# H22R2x_Frontend_2.net
KiCad netlist of a schematic drawn in Altium Designer
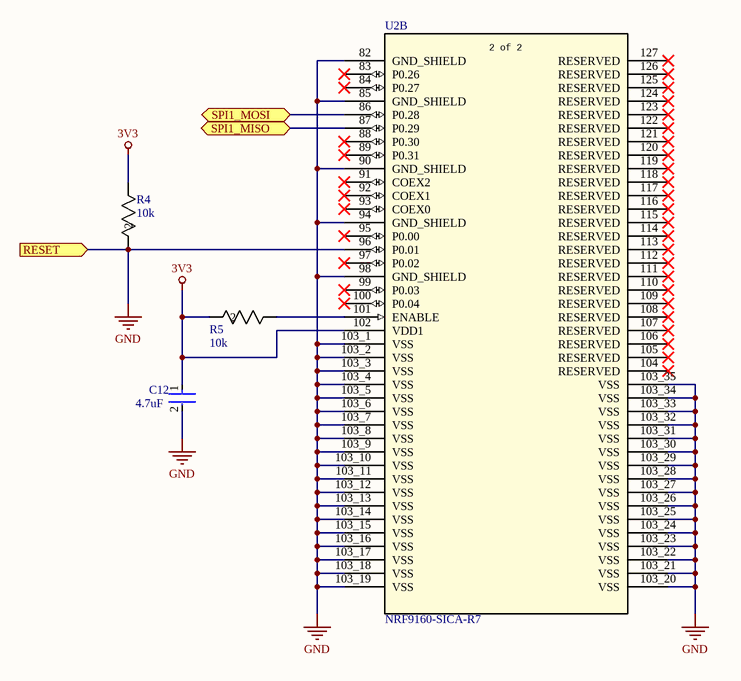
[diagram p0: H22R2x_Frontend 2.SchDoc]

(export (version "E")
  (design (tool "Eeschema 10.0.6"))
  (components
    (comp (ref "C12")
      (value "4.7uF")
      (footprint "FP-0603-L_1_6_0_15-W_0_8-MFG")
      (description "Ceramic Capacitor General Use 4.7uF ±10% 10V X6S 0603")
      (fields (field (name "TOLERANCE") "10%"))
      (libsource (lib "Altium Content Vault") (part "11868f565c42a9108669ba33697ecf6"))
    )
    (comp (ref "R4")
      (value "10k")
      (footprint "RC0201N_VIS")
      (description "CRCW0201 200 10K 1% ET7 e3")
      (fields
        (field (name "MANUFACTURER_PART_NUMBER") "CRCW020110K0FNED")
        (field (name "COPYRIGHT") "Copyright (C) 2025 Ultra Librarian. All rights reserved.")
      )
      (libsource (lib "Tyme Hopkins") (part "CRCW020110K0FNED"))
    )
    (comp (ref "R5")
      (value "10k")
      (footprint "RC0201N_VIS")
      (description "CRCW0201 200 10K 1% ET7 e3")
      (fields
        (field (name "MANUFACTURER_PART_NUMBER") "CRCW020110K0FNED")
        (field (name "COPYRIGHT") "Copyright (C) 2025 Ultra Librarian. All rights reserved.")
      )
      (libsource (lib "Tyme Hopkins") (part "CRCW020110K0FNED"))
    )
    (comp (ref "U2")
      (value "NRF9160-SICA-R7")
      (footprint "LGA127_16p00X10p50_nRF9160_NOR")
      (description "Description")
      (fields (field (name "COPYRIGHT") "Copyright (C) 2025 Ultra Librarian. All rights reserved."))
      (libsource (lib "Tyme Hopkins") (part "NRF9160-SICA-R7"))
    )
  )
  (nets
    (net (code "1") (name "/SPI1_MISO") (class "Default")
      (node (ref "U2") (pin "87") (pinfunction "P0.29_87") (pintype "bidirectional"))
    )
    (net (code "2") (name "/SPI1_MOSI") (class "Default")
      (node (ref "U2") (pin "86") (pinfunction "P0.28_86") (pintype "bidirectional"))
    )
    (net (code "3") (name "3V3") (class "Default")
      (node (ref "C12") (pin "1") (pinfunction "1_1") (pintype "passive"))
      (node (ref "R4") (pin "1") (pinfunction "1_1") (pintype "passive"))
      (node (ref "R5") (pin "2") (pinfunction "2_2") (pintype "passive"))
      (node (ref "U2") (pin "102") (pinfunction "VDD1_102") (pintype "power_in"))
    )
    (net (code "4") (name "GND") (class "Default")
      (node (ref "C12") (pin "2") (pinfunction "2_2") (pintype "passive"))
      (node (ref "R4") (pin "2") (pinfunction "2_2") (pintype "passive"))
      (node (ref "U2") (pin "103_1") (pinfunction "VSS_103_1") (pintype "power_in"))
      (node (ref "U2") (pin "103_10") (pinfunction "VSS_103_10") (pintype "power_in"))
      (node (ref "U2") (pin "103_11") (pinfunction "VSS_103_11") (pintype "power_in"))
      (node (ref "U2") (pin "103_12") (pinfunction "VSS_103_12") (pintype "power_in"))
      (node (ref "U2") (pin "103_13") (pinfunction "VSS_103_13") (pintype "power_in"))
      (node (ref "U2") (pin "103_14") (pinfunction "VSS_103_14") (pintype "power_in"))
      (node (ref "U2") (pin "103_15") (pinfunction "VSS_103_15") (pintype "power_in"))
      (node (ref "U2") (pin "103_16") (pinfunction "VSS_103_16") (pintype "power_in"))
      (node (ref "U2") (pin "103_17") (pinfunction "VSS_103_17") (pintype "power_in"))
      (node (ref "U2") (pin "103_18") (pinfunction "VSS_103_18") (pintype "power_in"))
      (node (ref "U2") (pin "103_19") (pinfunction "VSS_103_19") (pintype "power_in"))
      (node (ref "U2") (pin "103_2") (pinfunction "VSS_103_2") (pintype "power_in"))
      (node (ref "U2") (pin "103_20") (pinfunction "VSS_103_20") (pintype "power_in"))
      (node (ref "U2") (pin "103_21") (pinfunction "VSS_103_21") (pintype "power_in"))
      (node (ref "U2") (pin "103_22") (pinfunction "VSS_103_22") (pintype "power_in"))
      (node (ref "U2") (pin "103_23") (pinfunction "VSS_103_23") (pintype "power_in"))
      (node (ref "U2") (pin "103_24") (pinfunction "VSS_103_24") (pintype "power_in"))
      (node (ref "U2") (pin "103_25") (pinfunction "VSS_103_25") (pintype "power_in"))
      (node (ref "U2") (pin "103_26") (pinfunction "VSS_103_26") (pintype "power_in"))
      (node (ref "U2") (pin "103_27") (pinfunction "VSS_103_27") (pintype "power_in"))
      (node (ref "U2") (pin "103_28") (pinfunction "VSS_103_28") (pintype "power_in"))
      (node (ref "U2") (pin "103_29") (pinfunction "VSS_103_29") (pintype "power_in"))
      (node (ref "U2") (pin "103_3") (pinfunction "VSS_103_3") (pintype "power_in"))
      (node (ref "U2") (pin "103_30") (pinfunction "VSS_103_30") (pintype "power_in"))
      (node (ref "U2") (pin "103_31") (pinfunction "VSS_103_31") (pintype "power_in"))
      (node (ref "U2") (pin "103_32") (pinfunction "VSS_103_32") (pintype "power_in"))
      (node (ref "U2") (pin "103_33") (pinfunction "VSS_103_33") (pintype "power_in"))
      (node (ref "U2") (pin "103_34") (pinfunction "VSS_103_34") (pintype "power_in"))
      (node (ref "U2") (pin "103_35") (pinfunction "VSS_103_35") (pintype "power_in"))
      (node (ref "U2") (pin "103_4") (pinfunction "VSS_103_4") (pintype "power_in"))
      (node (ref "U2") (pin "103_5") (pinfunction "VSS_103_5") (pintype "power_in"))
      (node (ref "U2") (pin "103_6") (pinfunction "VSS_103_6") (pintype "power_in"))
      (node (ref "U2") (pin "103_7") (pinfunction "VSS_103_7") (pintype "power_in"))
      (node (ref "U2") (pin "103_8") (pinfunction "VSS_103_8") (pintype "power_in"))
      (node (ref "U2") (pin "103_9") (pinfunction "VSS_103_9") (pintype "power_in"))
      (node (ref "U2") (pin "82") (pinfunction "GND_SHIELD_82") (pintype "power_in"))
      (node (ref "U2") (pin "85") (pinfunction "GND_SHIELD_85") (pintype "power_in"))
      (node (ref "U2") (pin "90") (pinfunction "GND_SHIELD_90") (pintype "power_in"))
      (node (ref "U2") (pin "94") (pinfunction "GND_SHIELD_94") (pintype "power_in"))
      (node (ref "U2") (pin "96") (pinfunction "P0.01_96") (pintype "bidirectional"))
      (node (ref "U2") (pin "98") (pinfunction "GND_SHIELD_98") (pintype "power_in"))
    )
    (net (code "5") (name "Net-(U2B-ENABLE)") (class "Default")
      (node (ref "R5") (pin "1") (pinfunction "1_1") (pintype "passive"))
      (node (ref "U2") (pin "101") (pinfunction "ENABLE_101") (pintype "input"))
    )
    (net (code "6") (name "unconnected-(U2B-COEX0-Pad93)") (class "Default")
      (node (ref "U2") (pin "93") (pinfunction "COEX0_93") (pintype "bidirectional+no_connect"))
    )
    (net (code "7") (name "unconnected-(U2B-COEX1-Pad92)") (class "Default")
      (node (ref "U2") (pin "92") (pinfunction "COEX1_92") (pintype "bidirectional+no_connect"))
    )
    (net (code "8") (name "unconnected-(U2B-COEX2-Pad91)") (class "Default")
      (node (ref "U2") (pin "91") (pinfunction "COEX2_91") (pintype "bidirectional+no_connect"))
    )
    (net (code "9") (name "unconnected-(U2B-P0.00-Pad95)") (class "Default")
      (node (ref "U2") (pin "95") (pinfunction "P0.00_95") (pintype "bidirectional+no_connect"))
    )
    (net (code "10") (name "unconnected-(U2B-P0.02-Pad97)") (class "Default")
      (node (ref "U2") (pin "97") (pinfunction "P0.02_97") (pintype "bidirectional+no_connect"))
    )
    (net (code "11") (name "unconnected-(U2B-P0.03-Pad99)") (class "Default")
      (node (ref "U2") (pin "99") (pinfunction "P0.03_99") (pintype "bidirectional+no_connect"))
    )
    (net (code "12") (name "unconnected-(U2B-P0.04-Pad100)") (class "Default")
      (node (ref "U2") (pin "100") (pinfunction "P0.04_100") (pintype "bidirectional+no_connect"))
    )
    (net (code "13") (name "unconnected-(U2B-P0.26-Pad83)") (class "Default")
      (node (ref "U2") (pin "83") (pinfunction "P0.26_83") (pintype "bidirectional+no_connect"))
    )
    (net (code "14") (name "unconnected-(U2B-P0.27-Pad84)") (class "Default")
      (node (ref "U2") (pin "84") (pinfunction "P0.27_84") (pintype "bidirectional+no_connect"))
    )
    (net (code "15") (name "unconnected-(U2B-P0.30-Pad88)") (class "Default")
      (node (ref "U2") (pin "88") (pinfunction "P0.30_88") (pintype "bidirectional+no_connect"))
    )
    (net (code "16") (name "unconnected-(U2B-P0.31-Pad89)") (class "Default")
      (node (ref "U2") (pin "89") (pinfunction "P0.31_89") (pintype "bidirectional+no_connect"))
    )
    (net (code "17") (name "unconnected-(U2B-RESERVED-Pad104)") (class "Default")
      (node (ref "U2") (pin "104") (pinfunction "RESERVED_104") (pintype "passive+no_connect"))
    )
    (net (code "18") (name "unconnected-(U2B-RESERVED-Pad105)") (class "Default")
      (node (ref "U2") (pin "105") (pinfunction "RESERVED_105") (pintype "passive+no_connect"))
    )
    (net (code "19") (name "unconnected-(U2B-RESERVED-Pad106)") (class "Default")
      (node (ref "U2") (pin "106") (pinfunction "RESERVED_106") (pintype "passive+no_connect"))
    )
    (net (code "20") (name "unconnected-(U2B-RESERVED-Pad107)") (class "Default")
      (node (ref "U2") (pin "107") (pinfunction "RESERVED_107") (pintype "passive+no_connect"))
    )
    (net (code "21") (name "unconnected-(U2B-RESERVED-Pad108)") (class "Default")
      (node (ref "U2") (pin "108") (pinfunction "RESERVED_108") (pintype "passive+no_connect"))
    )
    (net (code "22") (name "unconnected-(U2B-RESERVED-Pad109)") (class "Default")
      (node (ref "U2") (pin "109") (pinfunction "RESERVED_109") (pintype "passive+no_connect"))
    )
    (net (code "23") (name "unconnected-(U2B-RESERVED-Pad110)") (class "Default")
      (node (ref "U2") (pin "110") (pinfunction "RESERVED_110") (pintype "passive+no_connect"))
    )
    (net (code "24") (name "unconnected-(U2B-RESERVED-Pad111)") (class "Default")
      (node (ref "U2") (pin "111") (pinfunction "RESERVED_111") (pintype "passive+no_connect"))
    )
    (net (code "25") (name "unconnected-(U2B-RESERVED-Pad112)") (class "Default")
      (node (ref "U2") (pin "112") (pinfunction "RESERVED_112") (pintype "passive+no_connect"))
    )
    (net (code "26") (name "unconnected-(U2B-RESERVED-Pad113)") (class "Default")
      (node (ref "U2") (pin "113") (pinfunction "RESERVED_113") (pintype "passive+no_connect"))
    )
    (net (code "27") (name "unconnected-(U2B-RESERVED-Pad114)") (class "Default")
      (node (ref "U2") (pin "114") (pinfunction "RESERVED_114") (pintype "passive+no_connect"))
    )
    (net (code "28") (name "unconnected-(U2B-RESERVED-Pad115)") (class "Default")
      (node (ref "U2") (pin "115") (pinfunction "RESERVED_115") (pintype "passive+no_connect"))
    )
    (net (code "29") (name "unconnected-(U2B-RESERVED-Pad116)") (class "Default")
      (node (ref "U2") (pin "116") (pinfunction "RESERVED_116") (pintype "passive+no_connect"))
    )
    (net (code "30") (name "unconnected-(U2B-RESERVED-Pad117)") (class "Default")
      (node (ref "U2") (pin "117") (pinfunction "RESERVED_117") (pintype "passive+no_connect"))
    )
    (net (code "31") (name "unconnected-(U2B-RESERVED-Pad118)") (class "Default")
      (node (ref "U2") (pin "118") (pinfunction "RESERVED_118") (pintype "passive+no_connect"))
    )
    (net (code "32") (name "unconnected-(U2B-RESERVED-Pad119)") (class "Default")
      (node (ref "U2") (pin "119") (pinfunction "RESERVED_119") (pintype "passive+no_connect"))
    )
    (net (code "33") (name "unconnected-(U2B-RESERVED-Pad120)") (class "Default")
      (node (ref "U2") (pin "120") (pinfunction "RESERVED_120") (pintype "passive+no_connect"))
    )
    (net (code "34") (name "unconnected-(U2B-RESERVED-Pad121)") (class "Default")
      (node (ref "U2") (pin "121") (pinfunction "RESERVED_121") (pintype "passive+no_connect"))
    )
    (net (code "35") (name "unconnected-(U2B-RESERVED-Pad122)") (class "Default")
      (node (ref "U2") (pin "122") (pinfunction "RESERVED_122") (pintype "passive+no_connect"))
    )
    (net (code "36") (name "unconnected-(U2B-RESERVED-Pad123)") (class "Default")
      (node (ref "U2") (pin "123") (pinfunction "RESERVED_123") (pintype "passive+no_connect"))
    )
    (net (code "37") (name "unconnected-(U2B-RESERVED-Pad124)") (class "Default")
      (node (ref "U2") (pin "124") (pinfunction "RESERVED_124") (pintype "passive+no_connect"))
    )
    (net (code "38") (name "unconnected-(U2B-RESERVED-Pad125)") (class "Default")
      (node (ref "U2") (pin "125") (pinfunction "RESERVED_125") (pintype "passive+no_connect"))
    )
    (net (code "39") (name "unconnected-(U2B-RESERVED-Pad126)") (class "Default")
      (node (ref "U2") (pin "126") (pinfunction "RESERVED_126") (pintype "passive+no_connect"))
    )
    (net (code "40") (name "unconnected-(U2B-RESERVED-Pad127)") (class "Default")
      (node (ref "U2") (pin "127") (pinfunction "RESERVED_127") (pintype "passive+no_connect"))
    )
  )
)
